# -_-.net
KiCad netlist of a schematic drawn in Altium Designer
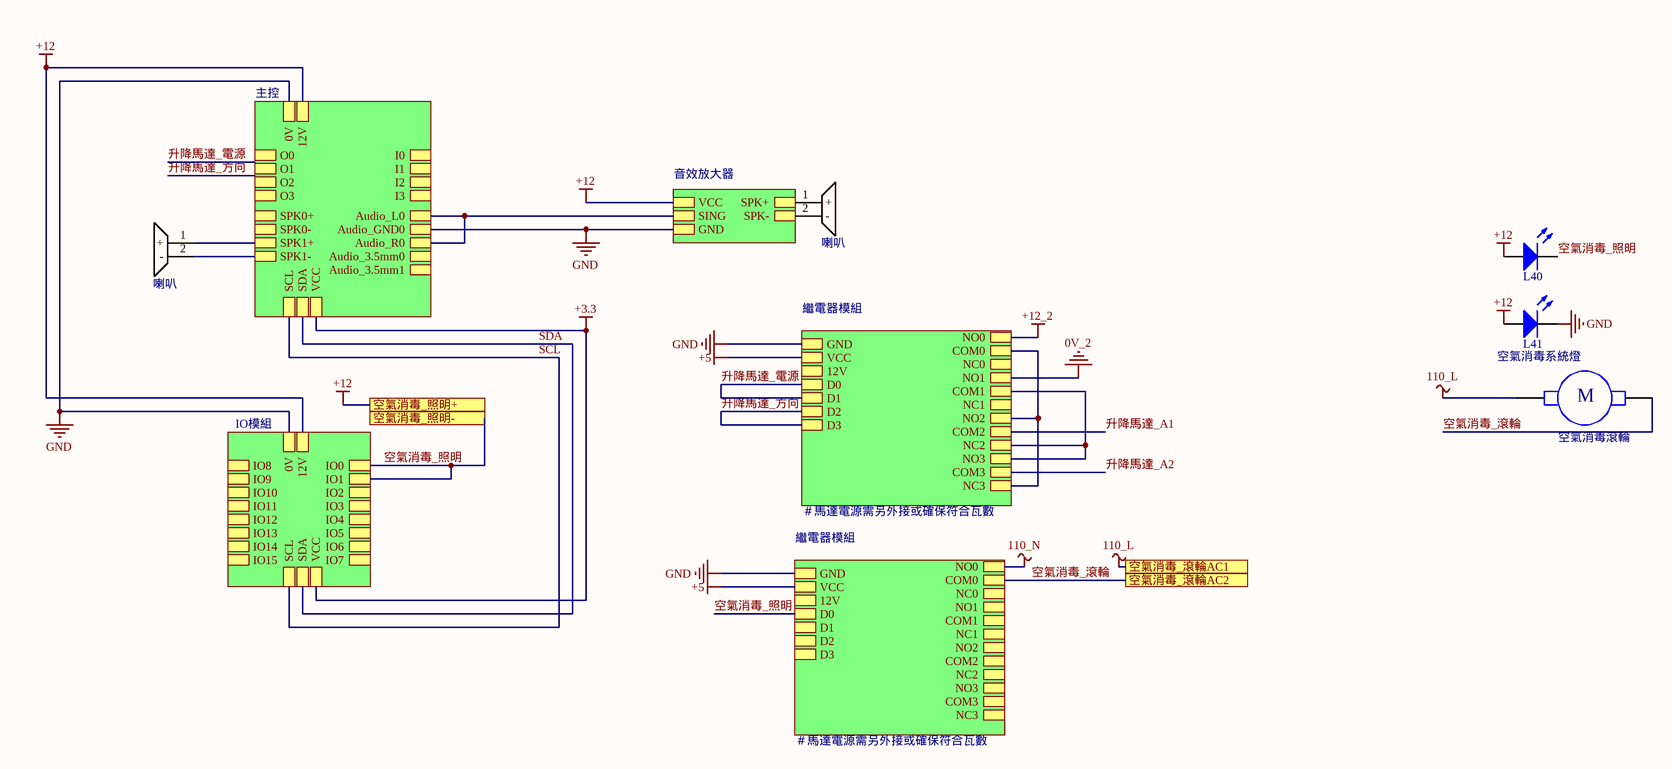
[diagram p0: 大直-絕境擴散-空氣消毒系統.SchDoc]

(export (version "E")
  (design (tool "Eeschema 10.0.6"))
  (components
    (comp (ref "B14")
      (value "喇叭")
      (footprint "Buzzer_12085")
      (description "無源蜂鳴器")
      (libsource (lib "MyLibray") (part "Buzzer"))
    )
    (comp (ref "B15")
      (value "喇叭")
      (footprint "Buzzer_12085")
      (description "無源蜂鳴器")
      (libsource (lib "MyLibray") (part "Buzzer"))
    )
    (comp (ref "L40")
      (value "藍")
      (footprint "LED-0603")
      (description "LED")
      (libsource (lib "MyLibray") (part "LED"))
    )
    (comp (ref "L41")
      (value "藍")
      (footprint "LED-0603")
      (description "LED")
      (libsource (lib "MyLibray") (part "LED"))
    )
    (comp (ref "MD3") (value "空氣消毒滾輪") (description "直流馬達") (libsource (lib "電機圖塊") (part "Motor_DC")))
  )
  (nets
    (net (code "3") (name "+12") (class "Default")
      (node (ref "L40") (pin "2") (pinfunction "A_2") (pintype "passive"))
      (node (ref "L41") (pin "2") (pinfunction "A_2") (pintype "passive"))
    )
    (net (code "51") (name "/SPK+") (class "Default")
      (node (ref "B14") (pin "1") (pinfunction "+_1") (pintype "passive"))
    )
    (net (code "52") (name "/SPK-") (class "Default")
      (node (ref "B14") (pin "2") (pinfunction "-_2") (pintype "passive"))
    )
    (net (code "55") (name "/SPK1+") (class "Default")
      (node (ref "B15") (pin "1") (pinfunction "+_1") (pintype "passive"))
    )
    (net (code "56") (name "/SPK1-") (class "Default")
      (node (ref "B15") (pin "2") (pinfunction "-_2") (pintype "passive"))
    )
    (net (code "61") (name "/空氣消毒_滾輪") (class "Default")
      (node (ref "MD3") (pin "4") (pinfunction "4_4") (pintype "power_in"))
    )
    (net (code "62") (name "/空氣消毒_照明") (class "Default")
      (node (ref "L40") (pin "1") (pinfunction "K_1") (pintype "passive"))
    )
    (net (code "64") (name "110_L") (class "Default")
      (node (ref "MD3") (pin "4") (pinfunction "4_4") (pintype "power_in"))
    )
    (net (code "66") (name "GND") (class "Default")
      (node (ref "L41") (pin "1") (pinfunction "K_1") (pintype "passive"))
    )
  )
)
